# Plumo-2D.net
KiCad netlist of a schematic drawn in Altium Designer
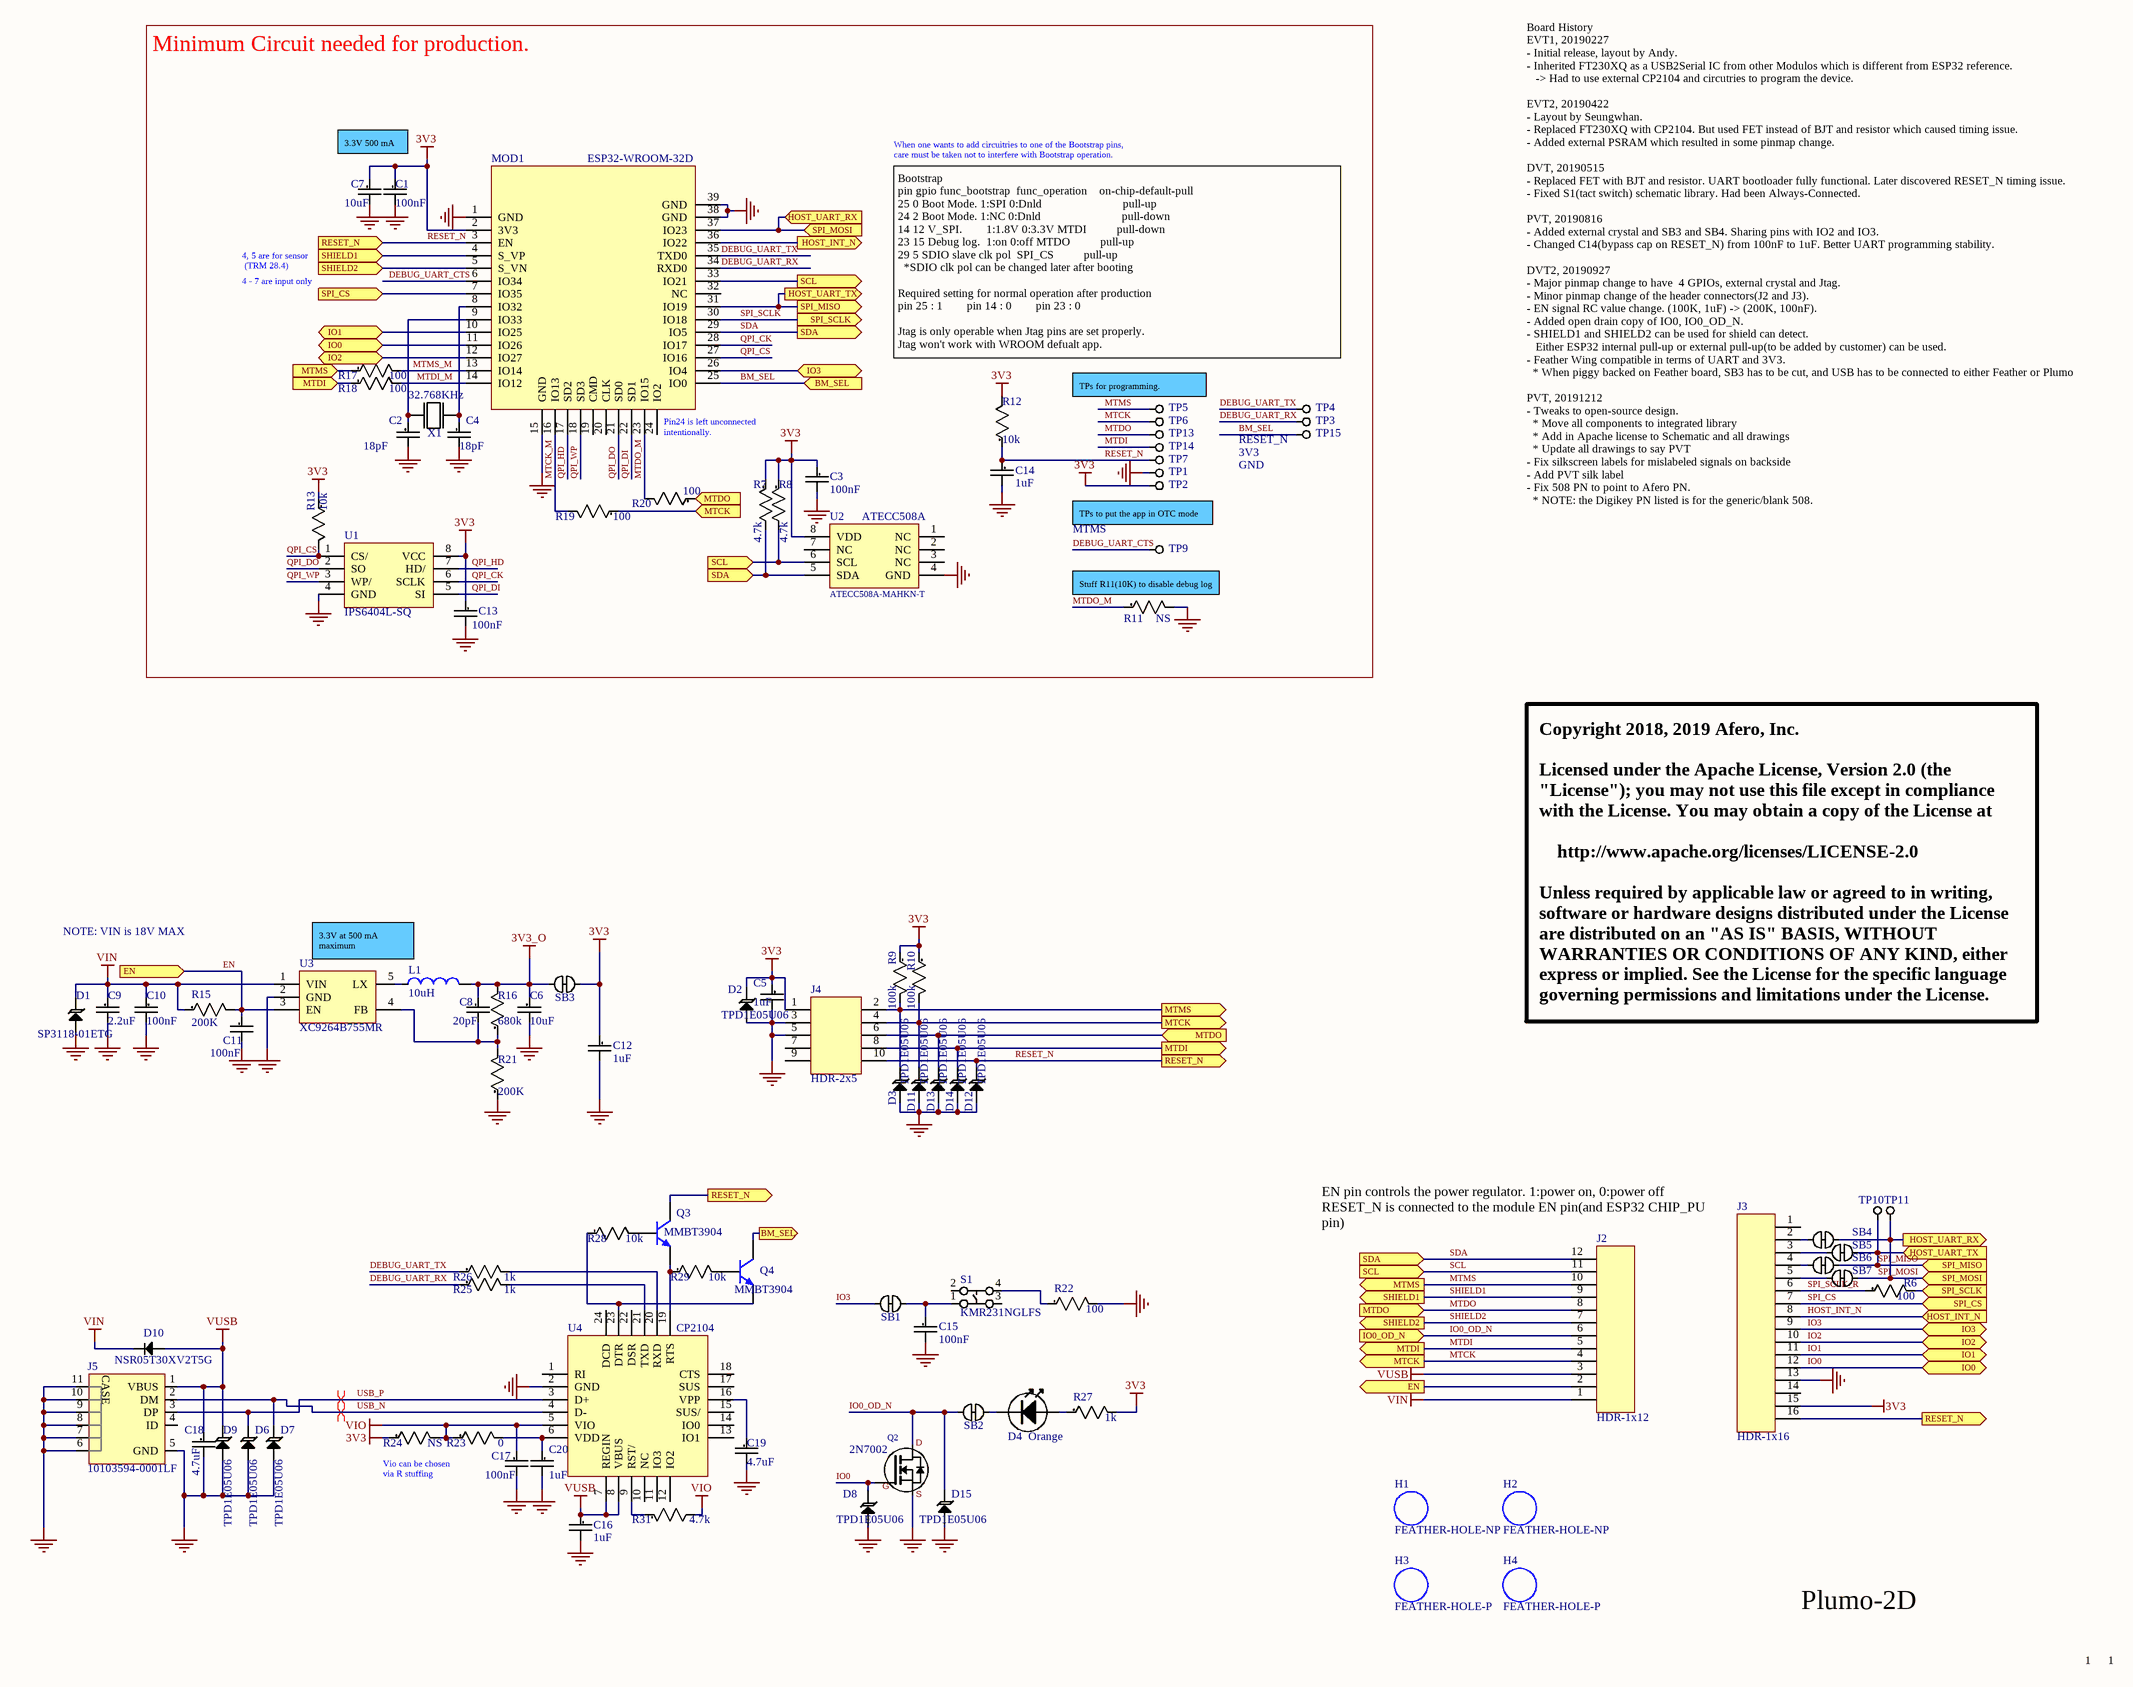
[diagram p0: Plumo-2D.SchDoc]

(export (version "E")
  (design (tool "Eeschema 10.0.6"))
  (components
    (comp (ref "C1")
      (value "100nF")
      (footprint "0402C-GENERIC")
      (description "Capacitor 100nF X5R 50V 10% 0402")
      (fields
        (field (name "MANUFACTURER") "Murata")
        (field (name "MANUFACTURER PART NUMBER") "GRM155R61H104KE19D")
      )
      (libsource (lib "Plumo-2D") (part "0402C-100n"))
    )
    (comp (ref "C2")
      (value "18pF")
      (footprint "0402C-GENERIC")
      (description "Capacitor, 18pF, 50V, 1%, C0G")
      (fields
        (field (name "MANUFACTURER") "Murata")
        (field (name "MANUFACTURER PART NUMBER") "GJM1555C1H180FB01D")
      )
      (libsource (lib "Plumo-2D") (part "0402C-18p"))
    )
    (comp (ref "C3")
      (value "100nF")
      (footprint "0402C-GENERIC")
      (description "Capacitor 100nF X5R 50V 10% 0402")
      (fields
        (field (name "MANUFACTURER") "Murata")
        (field (name "MANUFACTURER PART NUMBER") "GRM155R61H104KE19D")
      )
      (libsource (lib "Plumo-2D") (part "0402C-100n"))
    )
    (comp (ref "C4")
      (value "18pF")
      (footprint "0402C-GENERIC")
      (description "Capacitor, 18pF, 50V, 1%, C0G")
      (fields
        (field (name "MANUFACTURER") "Murata")
        (field (name "MANUFACTURER PART NUMBER") "GJM1555C1H180FB01D")
      )
      (libsource (lib "Plumo-2D") (part "0402C-18p"))
    )
    (comp (ref "C5")
      (value "1uF")
      (footprint "0402C-GENERIC")
      (description "Capacitor 1uF X5R 6.3V 20% 0402")
      (fields (field (name "MANUFACTURER") "SEM") (field (name "MANUFACTURER PART NUMBER") "CL05A105KQ5NNNC"))
      (libsource (lib "Plumo-2D") (part "0402C-1u"))
    )
    (comp (ref "C6")
      (value "10uF")
      (footprint "0603C-GENERIC")
      (description "Capacitor 10uF X5R 16V 20% 0603")
      (fields
        (field (name "MANUFACTURER") "Murata")
        (field (name "MANUFACTURER PART NUMBER") "GRM188R61C106MA73D")
      )
      (libsource (lib "Plumo-2D") (part "0603C-10u"))
    )
    (comp (ref "C7")
      (value "10uF")
      (footprint "0603C-GENERIC")
      (description "Capacitor 10uF X5R 16V 20% 0603")
      (fields
        (field (name "MANUFACTURER") "Murata")
        (field (name "MANUFACTURER PART NUMBER") "GRM188R61C106MA73D")
      )
      (libsource (lib "Plumo-2D") (part "0603C-10u"))
    )
    (comp (ref "C8")
      (value "20pF")
      (footprint "0402C-GENERIC")
      (description "Capacitor 20pF C0G 50V 1% 0402")
      (fields
        (field (name "MANUFACTURER") "Murata")
        (field (name "MANUFACTURER PART NUMBER") "GJM1555C1H200FB01D")
      )
      (libsource (lib "Plumo-2D") (part "0402C-20p"))
    )
    (comp (ref "C9")
      (value "2.2uF")
      (footprint "0603C-GENERIC")
      (description "Capacitor 2.2uF X5R 25V 10% 0603")
      (fields
        (field (name "MANUFACTURER") "Murata")
        (field (name "MANUFACTURER PART NUMBER") "GRM188R61E225KA12D")
      )
      (libsource (lib "Plumo-2D") (part "0603C-2u2"))
    )
    (comp (ref "C10")
      (value "100nF")
      (footprint "0402C-GENERIC")
      (description "Capacitor 100nF X5R 50V 10% 0402")
      (fields
        (field (name "MANUFACTURER") "Murata")
        (field (name "MANUFACTURER PART NUMBER") "GRM155R61H104KE19D")
      )
      (libsource (lib "Plumo-2D") (part "0402C-100n"))
    )
    (comp (ref "C11")
      (value "100nF")
      (footprint "0402C-GENERIC")
      (description "Capacitor 100nF X5R 50V 10% 0402")
      (fields
        (field (name "MANUFACTURER") "Murata")
        (field (name "MANUFACTURER PART NUMBER") "GRM155R61H104KE19D")
      )
      (libsource (lib "Plumo-2D") (part "0402C-100n"))
    )
    (comp (ref "C12")
      (value "1uF")
      (footprint "0402C-GENERIC")
      (description "Capacitor 1uF X5R 6.3V 20% 0402")
      (fields (field (name "MANUFACTURER") "SEM") (field (name "MANUFACTURER PART NUMBER") "CL05A105KQ5NNNC"))
      (libsource (lib "Plumo-2D") (part "0402C-1u"))
    )
    (comp (ref "C13")
      (value "100nF")
      (footprint "0402C-GENERIC")
      (description "Capacitor 100nF X5R 50V 10% 0402")
      (fields
        (field (name "MANUFACTURER") "Murata")
        (field (name "MANUFACTURER PART NUMBER") "GRM155R61H104KE19D")
      )
      (libsource (lib "Plumo-2D") (part "0402C-100n"))
    )
    (comp (ref "C14")
      (value "1uF")
      (footprint "0402C-GENERIC")
      (description "Capacitor 1uF X5R 6.3V 20% 0402")
      (fields (field (name "MANUFACTURER") "SEM") (field (name "MANUFACTURER PART NUMBER") "CL05A105KQ5NNNC"))
      (libsource (lib "Plumo-2D") (part "0402C-1u"))
    )
    (comp (ref "C15")
      (value "100nF")
      (footprint "0402C-GENERIC")
      (description "Capacitor 100nF X5R 50V 10% 0402")
      (fields
        (field (name "MANUFACTURER") "Murata")
        (field (name "MANUFACTURER PART NUMBER") "GRM155R61H104KE19D")
      )
      (libsource (lib "Plumo-2D") (part "0402C-100n"))
    )
    (comp (ref "C16")
      (value "1uF")
      (footprint "0402C-GENERIC")
      (description "Capacitor 1uF X5R 6.3V 20% 0402")
      (fields (field (name "MANUFACTURER") "SEM") (field (name "MANUFACTURER PART NUMBER") "CL05A105KQ5NNNC"))
      (libsource (lib "Plumo-2D") (part "0402C-1u"))
    )
    (comp (ref "C17")
      (value "100nF")
      (footprint "0402C-GENERIC")
      (description "Capacitor 100nF X5R 50V 10% 0402")
      (fields
        (field (name "MANUFACTURER") "Murata")
        (field (name "MANUFACTURER PART NUMBER") "GRM155R61H104KE19D")
      )
      (libsource (lib "Plumo-2D") (part "0402C-100n"))
    )
    (comp (ref "C18")
      (value "4.7uF")
      (footprint "0603C-GENERIC")
      (description "Capacitor 4.7uF X5R 10V 10% 0603")
      (fields
        (field (name "MANUFACTURER") "Taiyo Yuden")
        (field (name "MANUFACTURER PART NUMBER") "LMK107BJ475KA-T")
      )
      (libsource (lib "Plumo-2D") (part "0603C-4u7"))
    )
    (comp (ref "C19")
      (value "4.7uF")
      (footprint "0603C-GENERIC")
      (description "Capacitor 4.7uF X5R 10V 10% 0603")
      (fields
        (field (name "MANUFACTURER") "Taiyo Yuden")
        (field (name "MANUFACTURER PART NUMBER") "LMK107BJ475KA-T")
      )
      (libsource (lib "Plumo-2D") (part "0603C-4u7"))
    )
    (comp (ref "C20")
      (value "1uF")
      (footprint "0402C-GENERIC")
      (description "Capacitor 1uF X5R 6.3V 20% 0402")
      (fields (field (name "MANUFACTURER") "SEM") (field (name "MANUFACTURER PART NUMBER") "CL05A105KQ5NNNC"))
      (libsource (lib "Plumo-2D") (part "0402C-1u"))
    )
    (comp (ref "D1")
      (value "SP3118-01ETG")
      (footprint "SOD882")
      (description "Diode TVS")
      (fields (field (name "MANUFACTURER") "Littelfuse"))
      (libsource (lib "Plumo-2D") (part "SP3118-01ETG"))
    )
    (comp (ref "D2")
      (value "TPD1E05U06")
      (footprint "SON70P100X45-2N")
      (description "Diode TVS")
      (fields
        (field (name "MANUFACTURER") "Texas Instruments")
        (field (name "MANUFACTURER PART NUMBER") "TPD1E05U06DPYR")
      )
      (libsource (lib "Plumo-2D") (part "TPD1E05U06"))
    )
    (comp (ref "D3")
      (value "TPD1E05U06")
      (footprint "SON70P100X45-2N")
      (description "Diode TVS")
      (fields
        (field (name "MANUFACTURER") "Texas Instruments")
        (field (name "MANUFACTURER PART NUMBER") "TPD1E05U06DPYR")
      )
      (libsource (lib "Plumo-2D") (part "TPD1E05U06"))
    )
    (comp (ref "D4")
      (value "Orange")
      (footprint "0603LED")
      (description "LED Orange 0603")
      (fields
        (field (name "MANUFACTURER") "Vishay Lite-On")
        (field (name "MANUFACTURER PART NUMBER") "LTST-C190KAKT")
      )
      (libsource (lib "Plumo-2D") (part "LED_0603_O"))
    )
    (comp (ref "D6")
      (value "TPD1E05U06")
      (footprint "SON70P100X45-2N")
      (description "Diode TVS")
      (fields
        (field (name "MANUFACTURER") "Texas Instruments")
        (field (name "MANUFACTURER PART NUMBER") "TPD1E05U06DPYR")
      )
      (libsource (lib "Plumo-2D") (part "TPD1E05U06"))
    )
    (comp (ref "D7")
      (value "TPD1E05U06")
      (footprint "SON70P100X45-2N")
      (description "Diode TVS")
      (fields
        (field (name "MANUFACTURER") "Texas Instruments")
        (field (name "MANUFACTURER PART NUMBER") "TPD1E05U06DPYR")
      )
      (libsource (lib "Plumo-2D") (part "TPD1E05U06"))
    )
    (comp (ref "D8")
      (value "TPD1E05U06")
      (footprint "SON70P100X45-2N")
      (description "Diode TVS")
      (fields
        (field (name "MANUFACTURER") "Texas Instruments")
        (field (name "MANUFACTURER PART NUMBER") "TPD1E05U06DPYR")
      )
      (libsource (lib "Plumo-2D") (part "TPD1E05U06"))
    )
    (comp (ref "D9")
      (value "TPD1E05U06")
      (footprint "SON70P100X45-2N")
      (description "Diode TVS")
      (fields
        (field (name "MANUFACTURER") "Texas Instruments")
        (field (name "MANUFACTURER PART NUMBER") "TPD1E05U06DPYR")
      )
      (libsource (lib "Plumo-2D") (part "TPD1E05U06"))
    )
    (comp (ref "D10")
      (value "NSR05T30XV2T5G")
      (footprint "SOD-523")
      (description "Diode Schottky 30V 0.5A SOD523")
      (fields (field (name "MANUFACTURER") "On Semiconductor"))
      (libsource (lib "Plumo-2D") (part "NSR05T30XV2T5G"))
    )
    (comp (ref "D11")
      (value "TPD1E05U06")
      (footprint "SON70P100X45-2N")
      (description "Diode TVS")
      (fields
        (field (name "MANUFACTURER") "Texas Instruments")
        (field (name "MANUFACTURER PART NUMBER") "TPD1E05U06DPYR")
      )
      (libsource (lib "Plumo-2D") (part "TPD1E05U06"))
    )
    (comp (ref "D12")
      (value "TPD1E05U06")
      (footprint "SON70P100X45-2N")
      (description "Diode TVS")
      (fields
        (field (name "MANUFACTURER") "Texas Instruments")
        (field (name "MANUFACTURER PART NUMBER") "TPD1E05U06DPYR")
      )
      (libsource (lib "Plumo-2D") (part "TPD1E05U06"))
    )
    (comp (ref "D13")
      (value "TPD1E05U06")
      (footprint "SON70P100X45-2N")
      (description "Diode TVS")
      (fields
        (field (name "MANUFACTURER") "Texas Instruments")
        (field (name "MANUFACTURER PART NUMBER") "TPD1E05U06DPYR")
      )
      (libsource (lib "Plumo-2D") (part "TPD1E05U06"))
    )
    (comp (ref "D14")
      (value "TPD1E05U06")
      (footprint "SON70P100X45-2N")
      (description "Diode TVS")
      (fields
        (field (name "MANUFACTURER") "Texas Instruments")
        (field (name "MANUFACTURER PART NUMBER") "TPD1E05U06DPYR")
      )
      (libsource (lib "Plumo-2D") (part "TPD1E05U06"))
    )
    (comp (ref "D15")
      (value "TPD1E05U06")
      (footprint "SON70P100X45-2N")
      (description "Diode TVS")
      (fields
        (field (name "MANUFACTURER") "Texas Instruments")
        (field (name "MANUFACTURER PART NUMBER") "TPD1E05U06DPYR")
      )
      (libsource (lib "Plumo-2D") (part "TPD1E05U06"))
    )
    (comp (ref "H1")
      (value "FEATHER-HOLE-NP")
      (footprint "FEATHER-HOLE-NP")
      (description "0.09\" Unplated Hole")
      (libsource (lib "Plumo-2D") (part "FEATHER-HOLE-NP"))
    )
    (comp (ref "H2")
      (value "FEATHER-HOLE-NP")
      (footprint "FEATHER-HOLE-NP")
      (description "0.09\" Unplated Hole")
      (libsource (lib "Plumo-2D") (part "FEATHER-HOLE-NP"))
    )
    (comp (ref "H3")
      (value "FEATHER-HOLE-P")
      (footprint "FEATHER-HOLE-P")
      (description "0.1\" Plated Hole")
      (libsource (lib "Plumo-2D") (part "FEATHER-HOLE-P"))
    )
    (comp (ref "H4")
      (value "FEATHER-HOLE-P")
      (footprint "FEATHER-HOLE-P")
      (description "0.1\" Plated Hole")
      (libsource (lib "Plumo-2D") (part "FEATHER-HOLE-P"))
    )
    (comp (ref "J2")
      (value "HDR-1x12")
      (footprint "HDR-1X12")
      (description "0.1\" header 12 positions")
      (fields (field (name "MANUFACTURER PART NUMBER") "22032121") (field (name "MANUFACTURER") "Molex"))
      (libsource (lib "Plumo-2D") (part "HDR-1x12"))
    )
    (comp (ref "J3")
      (value "HDR-1x16")
      (footprint "HDR-1X16")
      (description "0.1\" header 16 positions")
      (fields (field (name "MANUFACTURER PART NUMBER") "22032161") (field (name "MANUFACTURER") "Molex"))
      (libsource (lib "Plumo-2D") (part "HDR-1x16"))
    )
    (comp (ref "J4")
      (value "HDR-2x5")
      (footprint "S9015E-05")
      (description ".050 Male Header 2x5")
      (fields (field (name "MANUFACTURER PART NUMBER") "GRPB052VWVN-RC"))
      (libsource (lib "Plumo-2D") (part "HDR-2x5"))
    )
    (comp (ref "J5")
      (value "10103594-0001LF")
      (footprint "10103594-0001LF")
      (description "Connector MICRO USB B")
      (fields (field (name "MANUFACTURER") "Amphenol FCI"))
      (libsource (lib "Plumo-2D") (part "10103594-0001LF"))
    )
    (comp (ref "L1")
      (value "10uH")
      (footprint "ASPI-0315FS")
      (description "Inductor 10uH 1.1A 0.22ohm 20% 3x3")
      (fields
        (field (name "MANUFACTURER") "Abracon")
        (field (name "MANUFACTURER PART NUMBER") "ASPI-0315FS-100M")
      )
      (libsource (lib "Plumo-2D") (part "ASPI-0315FS-100M"))
    )
    (comp (ref "MOD1")
      (value "ESP32-WROOM-32D")
      (footprint "ESP32-WROOM-32D")
      (description "Module WIFI BLE ESP32-D0WD 4MB")
      (fields (field (name "MANUFACTURER") "Espressif"))
      (libsource (lib "Plumo-2D") (part "ESP32-WROOM-32D"))
    )
    (comp (ref "Q2")
      (value "2N7002")
      (footprint "SOT23")
      (description "TR MOSFET N-CH 60V 115mA SOT23")
      (fields (field (name "MANUFACTURER") "On Semiconductor"))
      (libsource (lib "Plumo-2D") (part "Nch_MOSFET_2N7002"))
    )
    (comp (ref "Q3")
      (value "MMBT3904")
      (footprint "sot23")
      (description "TR NPN BJT 200mA 40V")
      (fields
        (field (name "MANUFACTURER PART NUMBER") "MMBT3904LT1G")
        (field (name "MANUFACTURER") "On Semiconductor")
      )
      (libsource (lib "Plumo-2D") (part "MMBT3904"))
    )
    (comp (ref "Q4")
      (value "MMBT3904")
      (footprint "sot23")
      (description "TR NPN BJT 200mA 40V")
      (fields
        (field (name "MANUFACTURER PART NUMBER") "MMBT3904LT1G")
        (field (name "MANUFACTURER") "On Semiconductor")
      )
      (libsource (lib "Plumo-2D") (part "MMBT3904"))
    )
    (comp (ref "R6")
      (value "100")
      (footprint "0402R-GENERIC")
      (description "Resistor 100R 50V 5% 0402")
      (fields
        (field (name "MANUFACTURER") "Panasonic")
        (field (name "MANUFACTURER PART NUMBER") "ERJ-2GEJ101X")
      )
      (libsource (lib "Plumo-2D") (part "0402R-100R"))
    )
    (comp (ref "R7")
      (value "4.7k")
      (footprint "0402R-GENERIC")
      (description "Resistor 4.7K 50V 5% 0402")
      (fields
        (field (name "MANUFACTURER") "Panasonic")
        (field (name "MANUFACTURER PART NUMBER") "ERJ-2GEJ472X")
      )
      (libsource (lib "Plumo-2D") (part "0402R-4k7"))
    )
    (comp (ref "R8")
      (value "4.7k")
      (footprint "0402R-GENERIC")
      (description "Resistor 4.7K 50V 5% 0402")
      (fields
        (field (name "MANUFACTURER") "Panasonic")
        (field (name "MANUFACTURER PART NUMBER") "ERJ-2GEJ472X")
      )
      (libsource (lib "Plumo-2D") (part "0402R-4k7"))
    )
    (comp (ref "R9")
      (value "100k")
      (footprint "0402R-GENERIC")
      (description "Resistor 100K 50V 5% 0402")
      (fields
        (field (name "MANUFACTURER") "Panasonic")
        (field (name "MANUFACTURER PART NUMBER") "ERJ-2GEJ104X")
      )
      (libsource (lib "Plumo-2D") (part "0402R-100k"))
    )
    (comp (ref "R10")
      (value "100k")
      (footprint "0402R-GENERIC")
      (description "Resistor 100K 50V 5% 0402")
      (fields
        (field (name "MANUFACTURER") "Panasonic")
        (field (name "MANUFACTURER PART NUMBER") "ERJ-2GEJ104X")
      )
      (libsource (lib "Plumo-2D") (part "0402R-100k"))
    )
    (comp (ref "R11")
      (value "NS")
      (footprint "0402R-GENERIC")
      (description "Resistor 0402 No Stuff")
      (fields (field (name "TOLERANCE") "1%"))
      (libsource (lib "Plumo-2D") (part "0402R-NS"))
    )
    (comp (ref "R12")
      (value "10k")
      (footprint "0402R-GENERIC")
      (description "Resistor 10K 50V 5% 0402")
      (fields
        (field (name "MANUFACTURER") "Vishay Dale")
        (field (name "MANUFACTURER PART NUMBER") "CRCW040210K0JNED")
      )
      (libsource (lib "Plumo-2D") (part "0402R-10k"))
    )
    (comp (ref "R13")
      (value "10k")
      (footprint "0402R-GENERIC")
      (description "Resistor 10K 50V 5% 0402")
      (fields
        (field (name "MANUFACTURER") "Vishay Dale")
        (field (name "MANUFACTURER PART NUMBER") "CRCW040210K0JNED")
      )
      (libsource (lib "Plumo-2D") (part "0402R-10k"))
    )
    (comp (ref "R15")
      (value "200K")
      (footprint "0402R-GENERIC")
      (description "Resistor 200K 50V 1% 0402")
      (fields
        (field (name "MANUFACTURER") "Panasonic")
        (field (name "MANUFACTURER PART NUMBER") "ERJ-2RKF2003X")
      )
      (libsource (lib "Plumo-2D") (part "0402R-200k"))
    )
    (comp (ref "R16")
      (value "680k")
      (footprint "0402R-GENERIC")
      (description "Resistor 680K 50V 5% 0402")
      (fields
        (field (name "MANUFACTURER") "Panasonic")
        (field (name "MANUFACTURER PART NUMBER") "ERJ-2GEJ684X")
      )
      (libsource (lib "Plumo-2D") (part "0402R-680k"))
    )
    (comp (ref "R17")
      (value "100")
      (footprint "0402R-GENERIC")
      (description "Resistor 100R 50V 5% 0402")
      (fields
        (field (name "MANUFACTURER") "Panasonic")
        (field (name "MANUFACTURER PART NUMBER") "ERJ-2GEJ101X")
      )
      (libsource (lib "Plumo-2D") (part "0402R-100R"))
    )
    (comp (ref "R18")
      (value "100")
      (footprint "0402R-GENERIC")
      (description "Resistor 100R 50V 5% 0402")
      (fields
        (field (name "MANUFACTURER") "Panasonic")
        (field (name "MANUFACTURER PART NUMBER") "ERJ-2GEJ101X")
      )
      (libsource (lib "Plumo-2D") (part "0402R-100R"))
    )
    (comp (ref "R19")
      (value "100")
      (footprint "0402R-GENERIC")
      (description "Resistor 100R 50V 5% 0402")
      (fields
        (field (name "MANUFACTURER") "Panasonic")
        (field (name "MANUFACTURER PART NUMBER") "ERJ-2GEJ101X")
      )
      (libsource (lib "Plumo-2D") (part "0402R-100R"))
    )
    (comp (ref "R20")
      (value "100")
      (footprint "0402R-GENERIC")
      (description "Resistor 100R 50V 5% 0402")
      (fields
        (field (name "MANUFACTURER") "Panasonic")
        (field (name "MANUFACTURER PART NUMBER") "ERJ-2GEJ101X")
      )
      (libsource (lib "Plumo-2D") (part "0402R-100R"))
    )
    (comp (ref "R21")
      (value "200K")
      (footprint "0402R-GENERIC")
      (description "Resistor 200K 50V 1% 0402")
      (fields
        (field (name "MANUFACTURER") "Panasonic")
        (field (name "MANUFACTURER PART NUMBER") "ERJ-2RKF2003X")
      )
      (libsource (lib "Plumo-2D") (part "0402R-200k"))
    )
    (comp (ref "R22")
      (value "100")
      (footprint "0402R-GENERIC")
      (description "Resistor 100R 50V 5% 0402")
      (fields
        (field (name "MANUFACTURER") "Panasonic")
        (field (name "MANUFACTURER PART NUMBER") "ERJ-2GEJ101X")
      )
      (libsource (lib "Plumo-2D") (part "0402R-100R"))
    )
    (comp (ref "R23")
      (value "0")
      (footprint "0402R-GENERIC")
      (description "Resistor 0R 50V 1% 0402")
      (fields
        (field (name "MANUFACTURER") "Yageo")
        (field (name "MANUFACTURER PART NUMBER") "RC0402FR-070RL")
      )
      (libsource (lib "Plumo-2D") (part "0402R-0R0"))
    )
    (comp (ref "R24")
      (value "NS")
      (footprint "0402R-GENERIC")
      (description "Resistor 0402 No Stuff")
      (fields (field (name "TOLERANCE") "1%"))
      (libsource (lib "Plumo-2D") (part "0402R-NS"))
    )
    (comp (ref "R25")
      (value "1k")
      (footprint "0402R-GENERIC")
      (description "Resistor 1K 50V 5% 0402")
      (fields
        (field (name "MANUFACTURER") "Panasonic")
        (field (name "MANUFACTURER PART NUMBER") "ERJ-2GEJ102X")
      )
      (libsource (lib "Plumo-2D") (part "0402R-1k"))
    )
    (comp (ref "R26")
      (value "1k")
      (footprint "0402R-GENERIC")
      (description "Resistor 1K 50V 5% 0402")
      (fields
        (field (name "MANUFACTURER") "Panasonic")
        (field (name "MANUFACTURER PART NUMBER") "ERJ-2GEJ102X")
      )
      (libsource (lib "Plumo-2D") (part "0402R-1k"))
    )
    (comp (ref "R27")
      (value "1k")
      (footprint "0402R-GENERIC")
      (description "Resistor 1K 50V 5% 0402")
      (fields
        (field (name "MANUFACTURER") "Panasonic")
        (field (name "MANUFACTURER PART NUMBER") "ERJ-2GEJ102X")
      )
      (libsource (lib "Plumo-2D") (part "0402R-1k"))
    )
    (comp (ref "R28")
      (value "10k")
      (footprint "0402R-GENERIC")
      (description "Resistor 10K 50V 5% 0402")
      (fields
        (field (name "MANUFACTURER") "Vishay Dale")
        (field (name "MANUFACTURER PART NUMBER") "CRCW040210K0JNED")
      )
      (libsource (lib "Plumo-2D") (part "0402R-10k"))
    )
    (comp (ref "R29")
      (value "10k")
      (footprint "0402R-GENERIC")
      (description "Resistor 10K 50V 5% 0402")
      (fields
        (field (name "MANUFACTURER") "Vishay Dale")
        (field (name "MANUFACTURER PART NUMBER") "CRCW040210K0JNED")
      )
      (libsource (lib "Plumo-2D") (part "0402R-10k"))
    )
    (comp (ref "R31")
      (value "4.7k")
      (footprint "0402R-GENERIC")
      (description "Resistor 4.7K 50V 5% 0402")
      (fields
        (field (name "MANUFACTURER") "Panasonic")
        (field (name "MANUFACTURER PART NUMBER") "ERJ-2GEJ472X")
      )
      (libsource (lib "Plumo-2D") (part "0402R-4k7"))
    )
    (comp (ref "S1")
      (value "KMR231NGLFS")
      (footprint "KMR231NGLFS")
      (description "SMD Tact Switch")
      (fields (field (name "MANUFACTURER") "ITT C&K"))
      (libsource (lib "Plumo-2D") (part "KMR231NGLFS"))
    )
    (comp (ref "SB1")
      (value "Solderbridge")
      (footprint "SBNC")
      (description "Solderbridge, Normally Closed")
      (fields (field (name "PART NUMBER") "Solderbridge Shorted"))
      (libsource (lib "Plumo-2D") (part "SBNC"))
    )
    (comp (ref "SB2")
      (value "Solderbridge")
      (footprint "SBNC")
      (description "Solderbridge, Normally Closed")
      (fields (field (name "PART NUMBER") "Solderbridge Shorted"))
      (libsource (lib "Plumo-2D") (part "SBNC"))
    )
    (comp (ref "SB3")
      (value "Solderbridge")
      (footprint "SBNC")
      (description "Solderbridge, Normally Closed")
      (fields (field (name "PART NUMBER") "Solderbridge Shorted"))
      (libsource (lib "Plumo-2D") (part "SBNC"))
    )
    (comp (ref "SB4")
      (value "Solderbridge")
      (footprint "SBNC")
      (description "Solderbridge, Normally Closed")
      (fields (field (name "PART NUMBER") "Solderbridge Shorted"))
      (libsource (lib "Plumo-2D") (part "SBNC"))
    )
    (comp (ref "SB5")
      (value "Solderbridge")
      (footprint "SBNC")
      (description "Solderbridge, Normally Closed")
      (fields (field (name "PART NUMBER") "Solderbridge Shorted"))
      (libsource (lib "Plumo-2D") (part "SBNC"))
    )
    (comp (ref "SB6")
      (value "Solderbridge")
      (footprint "SBNC")
      (description "Solderbridge, Normally Closed")
      (fields (field (name "PART NUMBER") "Solderbridge Shorted"))
      (libsource (lib "Plumo-2D") (part "SBNC"))
    )
    (comp (ref "SB7")
      (value "Solderbridge")
      (footprint "SBNC")
      (description "Solderbridge, Normally Closed")
      (fields (field (name "PART NUMBER") "Solderbridge Shorted"))
      (libsource (lib "Plumo-2D") (part "SBNC"))
    )
    (comp (ref "TP1")
      (value "TP1MM")
      (footprint "TP1MM")
      (description "1mm Test Point")
      (libsource (lib "Plumo-2D") (part "TP1MM"))
    )
    (comp (ref "TP2")
      (value "TP1MM")
      (footprint "TP1MM")
      (description "1mm Test Point")
      (libsource (lib "Plumo-2D") (part "TP1MM"))
    )
    (comp (ref "TP3")
      (value "TP1MM")
      (footprint "TP1MM")
      (description "1mm Test Point")
      (libsource (lib "Plumo-2D") (part "TP1MM"))
    )
    (comp (ref "TP4")
      (value "TP1MM")
      (footprint "TP1MM")
      (description "1mm Test Point")
      (libsource (lib "Plumo-2D") (part "TP1MM"))
    )
    (comp (ref "TP5")
      (value "TP1MM")
      (footprint "TP1MM")
      (description "1mm Test Point")
      (libsource (lib "Plumo-2D") (part "TP1MM"))
    )
    (comp (ref "TP6")
      (value "TP1MM")
      (footprint "TP1MM")
      (description "1mm Test Point")
      (libsource (lib "Plumo-2D") (part "TP1MM"))
    )
    (comp (ref "TP7")
      (value "TP1MM")
      (footprint "TP1MM")
      (description "1mm Test Point")
      (libsource (lib "Plumo-2D") (part "TP1MM"))
    )
    (comp (ref "TP9")
      (value "TP1MM")
      (footprint "TP1MM")
      (description "1mm Test Point")
      (libsource (lib "Plumo-2D") (part "TP1MM"))
    )
    (comp (ref "TP10")
      (value "TP1MM")
      (footprint "TP1MM")
      (description "1mm Test Point")
      (libsource (lib "Plumo-2D") (part "TP1MM"))
    )
    (comp (ref "TP11")
      (value "TP1MM")
      (footprint "TP1MM")
      (description "1mm Test Point")
      (libsource (lib "Plumo-2D") (part "TP1MM"))
    )
    (comp (ref "TP13")
      (value "TP1MM")
      (footprint "TP1MM")
      (description "1mm Test Point")
      (libsource (lib "Plumo-2D") (part "TP1MM"))
    )
    (comp (ref "TP14")
      (value "TP1MM")
      (footprint "TP1MM")
      (description "1mm Test Point")
      (libsource (lib "Plumo-2D") (part "TP1MM"))
    )
    (comp (ref "TP15")
      (value "TP1MM")
      (footprint "TP1MM")
      (description "1mm Test Point")
      (libsource (lib "Plumo-2D") (part "TP1MM"))
    )
    (comp (ref "U1")
      (value "IPS6404L-SQ")
      (footprint "IPUS.PSRAM")
      (description "Memory SPI/QPI PSRAM 8MB SOIC8 150mil")
      (fields
        (field (name "MANUFACTURER") "IPUS")
        (field (name "MANUFACTURER PART NUMBER") "IPS6404L-SQ-SPN")
      )
      (libsource (lib "Plumo-2D") (part "IPS6404L-SQ"))
    )
    (comp (ref "U2")
      (value "ATECC508A")
      (footprint "SON50P300X60-8N")
      (description "Afero Custom CryptoAuthentication Device")
      (fields
        (field (name "MANUFACTURER") "Microchip / Atmel")
        (field (name "MANUFACTURER PART NUMBER") "ATECC508A-MAHKN-T")
      )
      (libsource (lib "Plumo-2D") (part "ATECC508A"))
    )
    (comp (ref "U3")
      (value "XC9264B755MR")
      (footprint "SOT95P275X130-5N")
      (description "Voltage Regulator 0.5A 500KHz Buck")
      (fields (field (name "MANUFACTURER") "Torex"))
      (libsource (lib "Plumo-2D") (part "XC9264B755MR"))
    )
    (comp (ref "U4")
      (value "CP2104")
      (footprint "CP2104")
      (description "USB to UART Bridge")
      (fields
        (field (name "MANUFACTURER PART NUMBER") "CP2104-F03-GM")
        (field (name "MANUFACTURER") "SiLabs")
      )
      (libsource (lib "Plumo-2D") (part "CP2104"))
    )
    (comp (ref "X1")
      (value "32.768KHz")
      (footprint "ABS06")
      (description "Crystal, 32.768kHz ±20ppm")
      (fields
        (field (name "MANUFACTURER") "Abracon")
        (field (name "MANUFACTURER PART NUMBER") "ABS06-32.768KHZ-T")
      )
      (libsource (lib "Plumo-2D") (part "ABS06-32.768KHZ-T"))
    )
  )
  (nets
    (net (code "1") (name "/BM_SEL") (class "Default")
      (node (ref "MOD1") (pin "25") (pinfunction "IO0_25") (pintype "passive"))
      (node (ref "Q4") (pin "3") (pinfunction "C_3") (pintype "passive"))
      (node (ref "TP15") (pin "1") (pinfunction "1_1") (pintype "passive"))
    )
    (net (code "2") (name "/DEBUG_UART_CTS") (class "Default")
      (node (ref "MOD1") (pin "6") (pinfunction "IO34_6") (pintype "passive"))
      (node (ref "TP9") (pin "1") (pinfunction "1_1") (pintype "passive"))
    )
    (net (code "3") (name "/DEBUG_UART_RX") (class "Default")
      (node (ref "MOD1") (pin "34") (pinfunction "RXD0_34") (pintype "passive"))
      (node (ref "R25") (pin "1") (pinfunction "1_1") (pintype "passive"))
      (node (ref "TP3") (pin "1") (pinfunction "1_1") (pintype "passive"))
    )
    (net (code "4") (name "/DEBUG_UART_TX") (class "Default")
      (node (ref "MOD1") (pin "35") (pinfunction "TXD0_35") (pintype "passive"))
      (node (ref "R26") (pin "1") (pinfunction "1_1") (pintype "passive"))
      (node (ref "TP4") (pin "1") (pinfunction "1_1") (pintype "passive"))
    )
    (net (code "5") (name "/EN") (class "Default")
      (node (ref "C11") (pin "1") (pintype "passive"))
      (node (ref "J2") (pin "2") (pinfunction "2_2") (pintype "passive"))
      (node (ref "R15") (pin "2") (pinfunction "2_2") (pintype "passive"))
      (node (ref "U3") (pin "3") (pinfunction "EN_3") (pintype "passive"))
    )
    (net (code "6") (name "/HOST_INT_N") (class "Default")
      (node (ref "J3") (pin "8") (pinfunction "8_8") (pintype "passive"))
      (node (ref "MOD1") (pin "36") (pinfunction "IO22_36") (pintype "passive"))
    )
    (net (code "7") (name "/IO0") (class "Default")
      (node (ref "D8") (pin "1") (pinfunction "I/O_1") (pintype "passive"))
      (node (ref "J3") (pin "12") (pinfunction "12_12") (pintype "passive"))
      (node (ref "MOD1") (pin "11") (pinfunction "IO26_11") (pintype "passive"))
      (node (ref "Q2") (pin "1") (pinfunction "G_1") (pintype "passive"))
    )
    (net (code "8") (name "/IO0_OD_N") (class "Default")
      (node (ref "D15") (pin "1") (pinfunction "I/O_1") (pintype "passive"))
      (node (ref "J2") (pin "6") (pinfunction "6_6") (pintype "passive"))
      (node (ref "Q2") (pin "3") (pinfunction "D_3") (pintype "passive"))
      (node (ref "SB2") (pin "1") (pinfunction "0_1") (pintype "passive"))
    )
    (net (code "9") (name "/IO1") (class "Default")
      (node (ref "J3") (pin "11") (pinfunction "11_11") (pintype "passive"))
      (node (ref "MOD1") (pin "10") (pinfunction "IO25_10") (pintype "passive"))
    )
    (net (code "10") (name "/IO2") (class "Default")
      (node (ref "J3") (pin "10") (pinfunction "10_10") (pintype "passive"))
      (node (ref "MOD1") (pin "12") (pinfunction "IO27_12") (pintype "passive"))
    )
    (net (code "11") (name "/IO3") (class "Default")
      (node (ref "J3") (pin "9") (pinfunction "9_9") (pintype "passive"))
      (node (ref "MOD1") (pin "26") (pinfunction "IO4_26") (pintype "passive"))
      (node (ref "SB1") (pin "1") (pinfunction "0_1") (pintype "passive"))
    )
    (net (code "12") (name "/MTCK") (class "Default")
      (node (ref "D11") (pin "1") (pinfunction "I/O_1") (pintype "passive"))
      (node (ref "J2") (pin "4") (pinfunction "4_4") (pintype "passive"))
      (node (ref "J4") (pin "4") (pinfunction "4_4") (pintype "passive"))
      (node (ref "R10") (pin "2") (pinfunction "2_2") (pintype "passive"))
      (node (ref "R19") (pin "1") (pinfunction "1_1") (pintype "passive"))
      (node (ref "TP6") (pin "1") (pinfunction "1_1") (pintype "passive"))
    )
    (net (code "13") (name "/MTCK_M") (class "Default")
      (node (ref "MOD1") (pin "16") (pinfunction "IO13_16") (pintype "passive"))
      (node (ref "R19") (pin "2") (pinfunction "2_2") (pintype "passive"))
    )
    (net (code "14") (name "/MTDI") (class "Default")
      (node (ref "D14") (pin "1") (pinfunction "I/O_1") (pintype "passive"))
      (node (ref "J2") (pin "5") (pinfunction "5_5") (pintype "passive"))
      (node (ref "J4") (pin "8") (pinfunction "8_8") (pintype "passive"))
      (node (ref "R18") (pin "1") (pinfunction "1_1") (pintype "passive"))
      (node (ref "TP14") (pin "1") (pinfunction "1_1") (pintype "passive"))
    )
    (net (code "15") (name "/MTDI_M") (class "Default")
      (node (ref "MOD1") (pin "14") (pinfunction "IO12_14") (pintype "passive"))
      (node (ref "R18") (pin "2") (pinfunction "2_2") (pintype "passive"))
    )
    (net (code "16") (name "/MTDO") (class "Default")
      (node (ref "D13") (pin "1") (pinfunction "I/O_1") (pintype "passive"))
      (node (ref "J2") (pin "8") (pinfunction "8_8") (pintype "passive"))
      (node (ref "J4") (pin "6") (pinfunction "6_6") (pintype "passive"))
      (node (ref "R20") (pin "1") (pinfunction "1_1") (pintype "passive"))
      (node (ref "TP13") (pin "1") (pinfunction "1_1") (pintype "passive"))
    )
    (net (code "17") (name "/MTDO_M") (class "Default")
      (node (ref "MOD1") (pin "23") (pinfunction "IO15_23") (pintype "passive"))
      (node (ref "R11") (pin "1") (pinfunction "1_1") (pintype "passive"))
      (node (ref "R20") (pin "2") (pinfunction "2_2") (pintype "passive"))
    )
    (net (code "18") (name "/MTMS") (class "Default")
      (node (ref "D3") (pin "1") (pinfunction "I/O_1") (pintype "passive"))
      (node (ref "J2") (pin "10") (pinfunction "10_10") (pintype "passive"))
      (node (ref "J4") (pin "2") (pinfunction "2_2") (pintype "passive"))
      (node (ref "R17") (pin "1") (pinfunction "1_1") (pintype "passive"))
      (node (ref "R9") (pin "2") (pinfunction "2_2") (pintype "passive"))
      (node (ref "TP5") (pin "1") (pinfunction "1_1") (pintype "passive"))
    )
    (net (code "19") (name "/MTMS_M") (class "Default")
      (node (ref "MOD1") (pin "13") (pinfunction "IO14_13") (pintype "passive"))
      (node (ref "R17") (pin "2") (pinfunction "2_2") (pintype "passive"))
    )
    (net (code "20") (name "/QPI_CK") (class "Default")
      (node (ref "MOD1") (pin "28") (pinfunction "IO17_28") (pintype "passive"))
      (node (ref "U1") (pin "6") (pinfunction "SCLK_6") (pintype "passive"))
    )
    (net (code "21") (name "/QPI_CS") (class "Default")
      (node (ref "MOD1") (pin "27") (pinfunction "IO16_27") (pintype "passive"))
      (node (ref "R13") (pin "2") (pinfunction "2_2") (pintype "passive"))
      (node (ref "U1") (pin "1") (pinfunction "CS/_1") (pintype "passive"))
    )
    (net (code "22") (name "/QPI_DI") (class "Default")
      (node (ref "MOD1") (pin "22") (pinfunction "SD1_22") (pintype "passive"))
      (node (ref "U1") (pin "5") (pinfunction "SI_5") (pintype "passive"))
    )
    (net (code "23") (name "/QPI_DO") (class "Default")
      (node (ref "MOD1") (pin "21") (pinfunction "SD0_21") (pintype "passive"))
      (node (ref "U1") (pin "2") (pinfunction "SO_2") (pintype "passive"))
    )
    (net (code "24") (name "/QPI_HD") (class "Default")
      (node (ref "MOD1") (pin "17") (pinfunction "SD2_17") (pintype "passive"))
      (node (ref "U1") (pin "7") (pinfunction "HD/_7") (pintype "passive"))
    )
    (net (code "25") (name "/QPI_WP") (class "Default")
      (node (ref "MOD1") (pin "18") (pinfunction "SD3_18") (pintype "passive"))
      (node (ref "U1") (pin "3") (pinfunction "WP/_3") (pintype "passive"))
    )
    (net (code "26") (name "/RESET_N") (class "Default")
      (node (ref "C14") (pin "1") (pintype "passive"))
      (node (ref "D12") (pin "1") (pinfunction "I/O_1") (pintype "passive"))
      (node (ref "J3") (pin "16") (pinfunction "16_16") (pintype "passive"))
      (node (ref "J4") (pin "10") (pinfunction "10_10") (pintype "passive"))
      (node (ref "MOD1") (pin "3") (pinfunction "EN_3") (pintype "passive"))
      (node (ref "Q3") (pin "3") (pinfunction "C_3") (pintype "passive"))
      (node (ref "R12") (pin "1") (pinfunction "1_1") (pintype "passive"))
      (node (ref "TP7") (pin "1") (pinfunction "1_1") (pintype "passive"))
    )
    (net (code "27") (name "/SCL") (class "Default")
      (node (ref "J2") (pin "11") (pinfunction "11_11") (pintype "passive"))
      (node (ref "MOD1") (pin "33") (pinfunction "IO21_33") (pintype "passive"))
      (node (ref "R8") (pin "2") (pinfunction "2_2") (pintype "passive"))
      (node (ref "U2") (pin "6") (pinfunction "SCL_6") (pintype "passive"))
    )
    (net (code "28") (name "/SDA") (class "Default")
      (node (ref "J2") (pin "12") (pinfunction "12_12") (pintype "passive"))
      (node (ref "MOD1") (pin "29") (pinfunction "IO5_29") (pintype "passive"))
      (node (ref "R7") (pin "2") (pinfunction "2_2") (pintype "passive"))
      (node (ref "U2") (pin "5") (pinfunction "SDA_5") (pintype "passive"))
    )
    (net (code "29") (name "/SHIELD1") (class "Default")
      (node (ref "J2") (pin "9") (pinfunction "9_9") (pintype "passive"))
      (node (ref "MOD1") (pin "4") (pinfunction "S_VP_4") (pintype "passive"))
    )
    (net (code "30") (name "/SHIELD2") (class "Default")
      (node (ref "J2") (pin "7") (pinfunction "7_7") (pintype "passive"))
      (node (ref "MOD1") (pin "5") (pinfunction "S_VN_5") (pintype "passive"))
    )
    (net (code "31") (name "/SPI_CS") (class "Default")
      (node (ref "J3") (pin "7") (pinfunction "7_7") (pintype "passive"))
      (node (ref "MOD1") (pin "7") (pinfunction "IO35_7") (pintype "passive"))
    )
    (net (code "32") (name "/SPI_MISO") (class "Default")
      (node (ref "MOD1") (pin "31") (pinfunction "IO19_31") (pintype "passive"))
      (node (ref "SB5") (pin "2") (pinfunction "1_2") (pintype "passive"))
      (node (ref "SB6") (pin "2") (pinfunction "1_2") (pintype "passive"))
      (node (ref "TP10") (pin "1") (pinfunction "1_1") (pintype "passive"))
    )
    (net (code "33") (name "/SPI_MOSI") (class "Default")
      (node (ref "MOD1") (pin "37") (pinfunction "IO23_37") (pintype "passive"))
      (node (ref "SB4") (pin "2") (pinfunction "1_2") (pintype "passive"))
      (node (ref "SB7") (pin "2") (pinfunction "1_2") (pintype "passive"))
      (node (ref "TP11") (pin "1") (pinfunction "1_1") (pintype "passive"))
    )
    (net (code "34") (name "/SPI_SCLK") (class "Default")
      (node (ref "MOD1") (pin "30") (pinfunction "IO18_30") (pintype "passive"))
      (node (ref "R6") (pin "2") (pinfunction "2_2") (pintype "passive"))
    )
    (net (code "35") (name "/SPI_SCLK_R") (class "Default")
      (node (ref "J3") (pin "6") (pinfunction "6_6") (pintype "passive"))
      (node (ref "R6") (pin "1") (pinfunction "1_1") (pintype "passive"))
    )
    (net (code "36") (name "/USB_N") (class "Default")
      (node (ref "D7") (pin "1") (pinfunction "I/O_1") (pintype "passive"))
      (node (ref "J5") (pin "2") (pinfunction "DM_2") (pintype "passive"))
      (node (ref "U4") (pin "4") (pinfunction "D-_4") (pintype "passive"))
    )
    (net (code "37") (name "/USB_P") (class "Default")
      (node (ref "D6") (pin "1") (pinfunction "I/O_1") (pintype "passive"))
      (node (ref "J5") (pin "3") (pinfunction "DP_3") (pintype "passive"))
      (node (ref "U4") (pin "3") (pinfunction "D+_3") (pintype "passive"))
    )
    (net (code "38") (name "3V3") (class "Default")
      (node (ref "C1") (pin "1") (pintype "passive"))
      (node (ref "C12") (pin "1") (pintype "passive"))
      (node (ref "C13") (pin "1") (pintype "passive"))
      (node (ref "C3") (pin "1") (pintype "passive"))
      (node (ref "C5") (pin "1") (pintype "passive"))
      (node (ref "C7") (pin "1") (pintype "passive"))
      (node (ref "D2") (pin "1") (pinfunction "I/O_1") (pintype "passive"))
      (node (ref "J3") (pin "15") (pinfunction "15_15") (pintype "passive"))
      (node (ref "J4") (pin "1") (pinfunction "1_1") (pintype "passive"))
      (node (ref "MOD1") (pin "2") (pinfunction "3V3_2") (pintype "passive"))
      (node (ref "R10") (pin "1") (pinfunction "1_1") (pintype "passive"))
      (node (ref "R12") (pin "2") (pinfunction "2_2") (pintype "passive"))
      (node (ref "R13") (pin "1") (pinfunction "1_1") (pintype "passive"))
      (node (ref "R24") (pin "1") (pinfunction "1_1") (pintype "passive"))
      (node (ref "R27") (pin "2") (pinfunction "2_2") (pintype "passive"))
      (node (ref "R7") (pin "1") (pinfunction "1_1") (pintype "passive"))
      (node (ref "R8") (pin "1") (pinfunction "1_1") (pintype "passive"))
      (node (ref "R9") (pin "1") (pinfunction "1_1") (pintype "passive"))
      (node (ref "SB3") (pin "1") (pinfunction "0_1") (pintype "passive"))
      (node (ref "TP2") (pin "1") (pinfunction "1_1") (pintype "passive"))
      (node (ref "U1") (pin "8") (pinfunction "VCC_8") (pintype "passive"))
      (node (ref "U2") (pin "8") (pinfunction "VDD_8") (pintype "power_in"))
    )
    (net (code "39") (name "3V3_O") (class "Default")
      (node (ref "C6") (pin "1") (pintype "passive"))
      (node (ref "C8") (pin "1") (pintype "passive"))
      (node (ref "L1") (pin "2") (pinfunction "2_2") (pintype "passive"))
      (node (ref "R16") (pin "2") (pinfunction "2_2") (pintype "passive"))
      (node (ref "SB3") (pin "2") (pinfunction "1_2") (pintype "passive"))
    )
    (net (code "40") (name "GND") (class "Default")
      (node (ref "C1") (pin "2") (pintype "passive"))
      (node (ref "C10") (pin "2") (pintype "passive"))
      (node (ref "C11") (pin "2") (pintype "passive"))
      (node (ref "C12") (pin "2") (pintype "passive"))
      (node (ref "C13") (pin "2") (pintype "passive"))
      (node (ref "C14") (pin "2") (pintype "passive"))
      (node (ref "C15") (pin "2") (pintype "passive"))
      (node (ref "C16") (pin "2") (pintype "passive"))
      (node (ref "C17") (pin "2") (pintype "passive"))
      (node (ref "C18") (pin "2") (pintype "passive"))
      (node (ref "C19") (pin "2") (pintype "passive"))
      (node (ref "C2") (pin "2") (pintype "passive"))
      (node (ref "C20") (pin "2") (pintype "passive"))
      (node (ref "C3") (pin "2") (pintype "passive"))
      (node (ref "C4") (pin "2") (pintype "passive"))
      (node (ref "C5") (pin "2") (pintype "passive"))
      (node (ref "C6") (pin "2") (pintype "passive"))
      (node (ref "C7") (pin "2") (pintype "passive"))
      (node (ref "C9") (pin "2") (pintype "passive"))
      (node (ref "D1") (pin "2") (pinfunction "GND_2") (pintype "passive"))
      (node (ref "D11") (pin "2") (pinfunction "GND_2") (pintype "passive"))
      (node (ref "D12") (pin "2") (pinfunction "GND_2") (pintype "passive"))
      (node (ref "D13") (pin "2") (pinfunction "GND_2") (pintype "passive"))
      (node (ref "D14") (pin "2") (pinfunction "GND_2") (pintype "passive"))
      (node (ref "D15") (pin "2") (pinfunction "GND_2") (pintype "passive"))
      (node (ref "D2") (pin "2") (pinfunction "GND_2") (pintype "passive"))
      (node (ref "D3") (pin "2") (pinfunction "GND_2") (pintype "passive"))
      (node (ref "D6") (pin "2") (pinfunction "GND_2") (pintype "passive"))
      (node (ref "D7") (pin "2") (pinfunction "GND_2") (pintype "passive"))
      (node (ref "D8") (pin "2") (pinfunction "GND_2") (pintype "passive"))
      (node (ref "D9") (pin "2") (pinfunction "GND_2") (pintype "passive"))
      (node (ref "J3") (pin "13") (pinfunction "13_13") (pintype "passive"))
      (node (ref "J4") (pin "3") (pinfunction "3_3") (pintype "passive"))
      (node (ref "J4") (pin "5") (pinfunction "5_5") (pintype "passive"))
      (node (ref "J5") (pin "10") (pinfunction "CASE_10") (pintype "passive"))
      (node (ref "J5") (pin "11") (pinfunction "CASE_11") (pintype "passive"))
      (node (ref "J5") (pin "5") (pinfunction "GND_5") (pintype "passive"))
      (node (ref "J5") (pin "6") (pinfunction "CASE_6") (pintype "passive"))
      (node (ref "J5") (pin "7") (pinfunction "CASE_7") (pintype "passive"))
      (node (ref "J5") (pin "8") (pinfunction "CASE_8") (pintype "passive"))
      (node (ref "J5") (pin "9") (pinfunction "CASE_9") (pintype "passive"))
      (node (ref "MOD1") (pin "1") (pinfunction "GND_1") (pintype "passive"))
      (node (ref "MOD1") (pin "15") (pinfunction "GND_15") (pintype "passive"))
      (node (ref "MOD1") (pin "38") (pinfunction "GND_38") (pintype "passive"))
      (node (ref "MOD1") (pin "39") (pinfunction "GND_39") (pintype "passive"))
      (node (ref "Q2") (pin "2") (pinfunction "S_2") (pintype "passive"))
      (node (ref "R11") (pin "2") (pinfunction "2_2") (pintype "passive"))
      (node (ref "R21") (pin "1") (pinfunction "1_1") (pintype "passive"))
      (node (ref "R22") (pin "2") (pinfunction "2_2") (pintype "passive"))
      (node (ref "TP1") (pin "1") (pinfunction "1_1") (pintype "passive"))
      (node (ref "U1") (pin "4") (pinfunction "GND_4") (pintype "passive"))
      (node (ref "U2") (pin "4") (pinfunction "GND_4") (pintype "power_in"))
      (node (ref "U3") (pin "2") (pinfunction "GND_2") (pintype "power_in"))
      (node (ref "U4") (pin "2") (pinfunction "GND_2") (pintype "passive"))
    )
    (net (code "41") (name "Net-(D4-PadA)") (class "Default")
      (node (ref "D4") (pin "A") (pintype "passive"))
      (node (ref "R27") (pin "1") (pinfunction "1_1") (pintype "passive"))
    )
    (net (code "42") (name "Net-(MOD1-IO32)") (class "Default")
      (node (ref "C4") (pin "1") (pintype "passive"))
      (node (ref "MOD1") (pin "8") (pinfunction "IO32_8") (pintype "passive"))
      (node (ref "X1") (pin "1") (pinfunction "1_1") (pintype "passive"))
    )
    (net (code "43") (name "Net-(MOD1-IO33)") (class "Default")
      (node (ref "C2") (pin "1") (pintype "passive"))
      (node (ref "MOD1") (pin "9") (pinfunction "IO33_9") (pintype "passive"))
      (node (ref "X1") (pin "2") (pinfunction "2_2") (pintype "passive"))
    )
    (net (code "44") (name "Net-(Q3-B)") (class "Default")
      (node (ref "Q3") (pin "1") (pinfunction "B_1") (pintype "passive"))
      (node (ref "R28") (pin "2") (pinfunction "2_2") (pintype "passive"))
    )
    (net (code "45") (name "Net-(Q3-E)") (class "Default")
      (node (ref "Q3") (pin "2") (pinfunction "E_2") (pintype "passive"))
      (node (ref "R29") (pin "1") (pinfunction "1_1") (pintype "passive"))
      (node (ref "U4") (pin "19") (pinfunction "RTS_19") (pintype "passive"))
    )
    (net (code "46") (name "Net-(Q4-B)") (class "Default")
      (node (ref "Q4") (pin "1") (pinfunction "B_1") (pintype "passive"))
      (node (ref "R29") (pin "2") (pinfunction "2_2") (pintype "passive"))
    )
    (net (code "47") (name "Net-(Q4-E)") (class "Default")
      (node (ref "Q4") (pin "2") (pinfunction "E_2") (pintype "passive"))
      (node (ref "R28") (pin "1") (pinfunction "1_1") (pintype "passive"))
      (node (ref "U4") (pin "23") (pinfunction "DTR_23") (pintype "passive"))
    )
    (net (code "48") (name "Net-(R22-Pad1)") (class "Default")
      (node (ref "R22") (pin "1") (pinfunction "1_1") (pintype "passive"))
      (node (ref "S1") (pin "4") (pinfunction "4_4") (pintype "passive"))
    )
    (net (code "49") (name "Net-(SB1-1)") (class "Default")
      (node (ref "C15") (pin "1") (pintype "passive"))
      (node (ref "S1") (pin "1") (pinfunction "1_1") (pintype "passive"))
      (node (ref "SB1") (pin "2") (pinfunction "1_2") (pintype "passive"))
    )
    (net (code "50") (name "Net-(SB2-1)") (class "Default")
      (node (ref "D4") (pin "K") (pintype "passive"))
      (node (ref "SB2") (pin "2") (pinfunction "1_2") (pintype "passive"))
    )
    (net (code "51") (name "Net-(SB4-0)") (class "Default")
      (node (ref "J3") (pin "2") (pinfunction "2_2") (pintype "passive"))
      (node (ref "SB4") (pin "1") (pinfunction "0_1") (pintype "passive"))
    )
    (net (code "52") (name "Net-(SB5-0)") (class "Default")
      (node (ref "J3") (pin "3") (pinfunction "3_3") (pintype "passive"))
      (node (ref "SB5") (pin "1") (pinfunction "0_1") (pintype "passive"))
    )
    (net (code "53") (name "Net-(SB6-0)") (class "Default")
      (node (ref "J3") (pin "4") (pinfunction "4_4") (pintype "passive"))
      (node (ref "SB6") (pin "1") (pinfunction "0_1") (pintype "passive"))
    )
    (net (code "54") (name "Net-(SB7-0)") (class "Default")
      (node (ref "J3") (pin "5") (pinfunction "5_5") (pintype "passive"))
      (node (ref "SB7") (pin "1") (pinfunction "0_1") (pintype "passive"))
    )
    (net (code "55") (name "Net-(U3-FB)") (class "Default")
      (node (ref "C8") (pin "2") (pintype "passive"))
      (node (ref "R16") (pin "1") (pinfunction "1_1") (pintype "passive"))
      (node (ref "R21") (pin "2") (pinfunction "2_2") (pintype "passive"))
      (node (ref "U3") (pin "4") (pinfunction "FB_4") (pintype "passive"))
    )
    (net (code "56") (name "Net-(U3-LX)") (class "Default")
      (node (ref "L1") (pin "1") (pinfunction "1_1") (pintype "passive"))
      (node (ref "U3") (pin "5") (pinfunction "LX_5") (pintype "passive"))
    )
    (net (code "57") (name "Net-(U4-RST{slash})") (class "Default")
      (node (ref "R31") (pin "1") (pinfunction "1_1") (pintype "passive"))
      (node (ref "U4") (pin "9") (pinfunction "RST/_9") (pintype "passive"))
    )
    (net (code "58") (name "Net-(U4-RXD)") (class "Default")
      (node (ref "R26") (pin "2") (pinfunction "2_2") (pintype "passive"))
      (node (ref "U4") (pin "20") (pinfunction "RXD_20") (pintype "passive"))
    )
    (net (code "59") (name "Net-(U4-TXD)") (class "Default")
      (node (ref "R25") (pin "2") (pinfunction "2_2") (pintype "passive"))
      (node (ref "U4") (pin "21") (pinfunction "TXD_21") (pintype "passive"))
    )
    (net (code "60") (name "Net-(U4-VDD)") (class "Default")
      (node (ref "C20") (pin "1") (pintype "passive"))
      (node (ref "R23") (pin "2") (pinfunction "2_2") (pintype "passive"))
      (node (ref "U4") (pin "6") (pinfunction "VDD_6") (pintype "passive"))
    )
    (net (code "61") (name "Net-(U4-VPP)") (class "Default")
      (node (ref "C19") (pin "1") (pintype "passive"))
      (node (ref "U4") (pin "16") (pinfunction "VPP_16") (pintype "passive"))
    )
    (net (code "62") (name "VIN") (class "Default")
      (node (ref "C10") (pin "1") (pintype "passive"))
      (node (ref "C9") (pin "1") (pintype "passive"))
      (node (ref "D1") (pin "1") (pinfunction "I/O_1") (pintype "passive"))
      (node (ref "D10") (pin "1") (pinfunction "I/O_1") (pintype "passive"))
      (node (ref "J2") (pin "1") (pinfunction "1_1") (pintype "passive"))
      (node (ref "R15") (pin "1") (pinfunction "1_1") (pintype "passive"))
      (node (ref "U3") (pin "1") (pinfunction "VIN_1") (pintype "power_in"))
    )
    (net (code "63") (name "VIO") (class "Default")
      (node (ref "C17") (pin "1") (pintype "passive"))
      (node (ref "R23") (pin "1") (pinfunction "1_1") (pintype "passive"))
      (node (ref "R24") (pin "2") (pinfunction "2_2") (pintype "passive"))
      (node (ref "R31") (pin "2") (pinfunction "2_2") (pintype "passive"))
      (node (ref "U4") (pin "5") (pinfunction "VIO_5") (pintype "passive"))
    )
    (net (code "64") (name "VUSB") (class "Default")
      (node (ref "C16") (pin "1") (pintype "passive"))
      (node (ref "C18") (pin "1") (pintype "passive"))
      (node (ref "D10") (pin "2") (pinfunction "GND_2") (pintype "passive"))
      (node (ref "D9") (pin "1") (pinfunction "I/O_1") (pintype "passive"))
      (node (ref "J2") (pin "3") (pinfunction "3_3") (pintype "passive"))
      (node (ref "J5") (pin "1") (pinfunction "VBUS_1") (pintype "passive"))
      (node (ref "U4") (pin "7") (pinfunction "REGIN_7") (pintype "passive"))
      (node (ref "U4") (pin "8") (pinfunction "VBUS_8") (pintype "passive"))
    )
    (net (code "65") (name "unconnected-(J3-Pad1)") (class "Default")
      (node (ref "J3") (pin "1") (pinfunction "1_1") (pintype "passive"))
    )
    (net (code "66") (name "unconnected-(J3-Pad14)") (class "Default")
      (node (ref "J3") (pin "14") (pinfunction "14_14") (pintype "passive"))
    )
    (net (code "67") (name "unconnected-(J4-Pad7)") (class "Default")
      (node (ref "J4") (pin "7") (pinfunction "7_7") (pintype "passive"))
    )
    (net (code "68") (name "unconnected-(J4-Pad9)") (class "Default")
      (node (ref "J4") (pin "9") (pinfunction "9_9") (pintype "passive"))
    )
    (net (code "69") (name "unconnected-(J5-ID-Pad4)") (class "Default")
      (node (ref "J5") (pin "4") (pinfunction "ID_4") (pintype "passive"))
    )
    (net (code "70") (name "unconnected-(MOD1-CLK-Pad20)") (class "Default")
      (node (ref "MOD1") (pin "20") (pinfunction "CLK_20") (pintype "passive"))
    )
    (net (code "71") (name "unconnected-(MOD1-CMD-Pad19)") (class "Default")
      (node (ref "MOD1") (pin "19") (pinfunction "CMD_19") (pintype "passive"))
    )
    (net (code "72") (name "unconnected-(MOD1-IO2-Pad24)") (class "Default")
      (node (ref "MOD1") (pin "24") (pinfunction "IO2_24") (pintype "passive"))
    )
    (net (code "73") (name "unconnected-(MOD1-NC-Pad32)") (class "Default")
      (node (ref "MOD1") (pin "32") (pinfunction "NC_32") (pintype "passive"))
    )
    (net (code "74") (name "unconnected-(S1-Pad2)") (class "Default")
      (node (ref "S1") (pin "2") (pinfunction "2_2") (pintype "passive"))
    )
    (net (code "75") (name "unconnected-(S1-Pad3)") (class "Default")
      (node (ref "S1") (pin "3") (pinfunction "3_3") (pintype "passive"))
    )
    (net (code "76") (name "unconnected-(U2-NC-Pad1)") (class "Default")
      (node (ref "U2") (pin "1") (pinfunction "NC_1") (pintype "passive"))
    )
    (net (code "77") (name "unconnected-(U2-NC-Pad2)") (class "Default")
      (node (ref "U2") (pin "2") (pinfunction "NC_2") (pintype "passive"))
    )
    (net (code "78") (name "unconnected-(U2-NC-Pad3)") (class "Default")
      (node (ref "U2") (pin "3") (pinfunction "NC_3") (pintype "passive"))
    )
    (net (code "79") (name "unconnected-(U2-NC-Pad7)") (class "Default")
      (node (ref "U2") (pin "7") (pinfunction "NC_7") (pintype "passive"))
    )
    (net (code "80") (name "unconnected-(U4-CTS-Pad18)") (class "Default")
      (node (ref "U4") (pin "18") (pinfunction "CTS_18") (pintype "passive"))
    )
    (net (code "81") (name "unconnected-(U4-DCD-Pad24)") (class "Default")
      (node (ref "U4") (pin "24") (pinfunction "DCD_24") (pintype "passive"))
    )
    (net (code "82") (name "unconnected-(U4-DSR-Pad22)") (class "Default")
      (node (ref "U4") (pin "22") (pinfunction "DSR_22") (pintype "passive"))
    )
    (net (code "83") (name "unconnected-(U4-IO0-Pad14)") (class "Default")
      (node (ref "U4") (pin "14") (pinfunction "IO0_14") (pintype "passive"))
    )
    (net (code "84") (name "unconnected-(U4-IO1-Pad13)") (class "Default")
      (node (ref "U4") (pin "13") (pinfunction "IO1_13") (pintype "passive"))
    )
    (net (code "85") (name "unconnected-(U4-IO2-Pad12)") (class "Default")
      (node (ref "U4") (pin "12") (pinfunction "IO2_12") (pintype "passive"))
    )
    (net (code "86") (name "unconnected-(U4-IO3-Pad11)") (class "Default")
      (node (ref "U4") (pin "11") (pinfunction "IO3_11") (pintype "passive"))
    )
    (net (code "87") (name "unconnected-(U4-NC-Pad10)") (class "Default")
      (node (ref "U4") (pin "10") (pinfunction "NC_10") (pintype "passive"))
    )
    (net (code "88") (name "unconnected-(U4-RI-Pad1)") (class "Default")
      (node (ref "U4") (pin "1") (pinfunction "RI_1") (pintype "passive"))
    )
    (net (code "89") (name "unconnected-(U4-SUS-Pad17)") (class "Default")
      (node (ref "U4") (pin "17") (pinfunction "SUS_17") (pintype "passive"))
    )
    (net (code "90") (name "unconnected-(U4-SUS{slash}-Pad15)") (class "Default")
      (node (ref "U4") (pin "15") (pinfunction "SUS/_15") (pintype "passive"))
    )
  )
)
